# Sheet1.net
KiCad netlist of a schematic drawn in Altium Designer
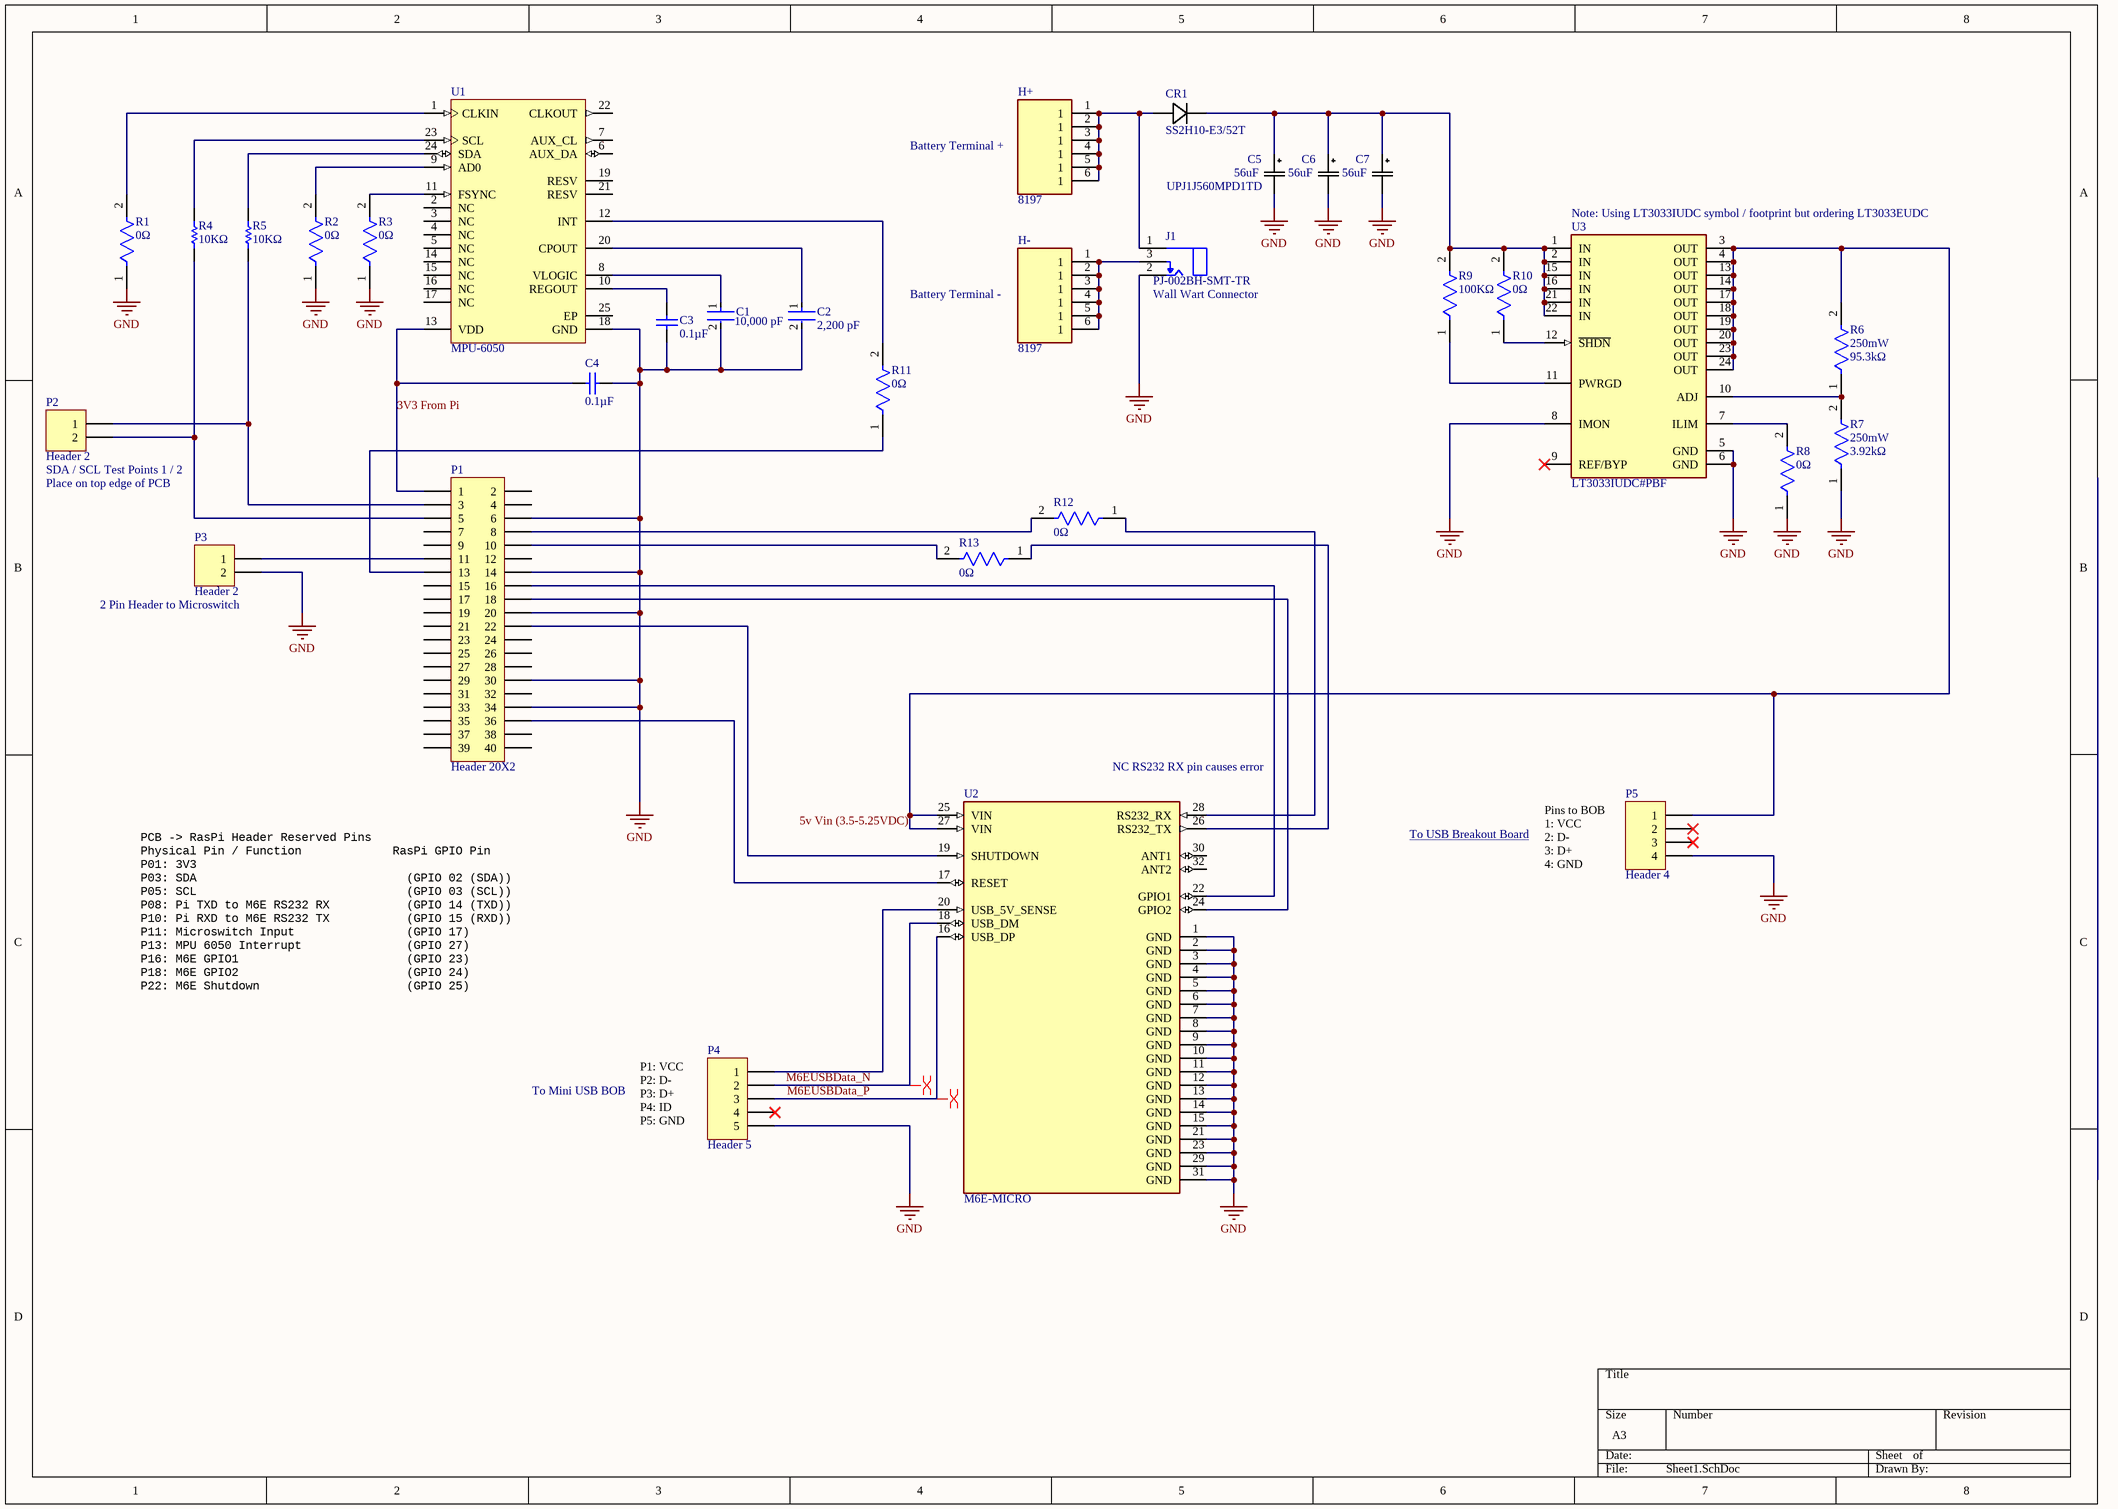
[diagram p0: Sheet1.SchDoc]

(export (version "E")
  (design (tool "Eeschema 10.0.6"))
  (components
    (comp (ref "C1")
      (value "C1206C103K1RACTU")
      (footprint "FP-C1206C-EB-MFG")
      (description "Cap Ceramic 0.01uF 100V X7R 10% SMD 1206 125°C Plastic T/R")
      (fields
        (field (name "MANUFACTURER") "KEMET")
        (field (name "OCTOPART") "https://octopart.com/c1206c103k1ractu-kemet-117927")
        (field (name "CAPACITANCE") "10,000 pF")
      )
      (libsource (lib "Altium Content Vault") (part "b4654b650e69147ec39a6b967a45e02"))
    )
    (comp (ref "C2")
      (value "2,200 pF")
      (footprint "FP-C1206C-EB-MFG")
      (description "CAP CER 2200PF 50V X7R 1206")
      (fields
        (field (name "MANUFACTURER") "KEMET")
        (field (name "MANUFACTURER PART NUMBER") "C1206C222K5RACTU")
      )
      (libsource (lib "Altium Content Vault") (part "b4654b650e69147ec39a6b967a45e02"))
    )
    (comp (ref "C3")
      (value "C1206C104K5RACTU")
      (footprint "KEMT-1206-2_M")
      (description "CAP, Ceramic, 0.1 uF, +/- 10%, 50 V, -55 to 125 degC, 1206 (3216 Metric), RoHS, Tape and Reel")
      (fields (field (name "CAPACITANCE") "0.1µF") (field (name "MANUFACTURER") "Kemet"))
      (libsource (lib "Altium Content Vault") (part "CAP-NP-2"))
    )
    (comp (ref "C4")
      (value "C1206C104K5RACTU")
      (footprint "KEMT-1206-2_M")
      (description "CAP, Ceramic, 0.1 uF, +/- 10%, 50 V, -55 to 125 degC, 1206 (3216 Metric), RoHS, Tape and Reel")
      (fields (field (name "CAPACITANCE") "0.1µF") (field (name "MANUFACTURER") "Kemet"))
      (libsource (lib "Altium Content Vault") (part "CAP-NP-2"))
    )
    (comp (ref "C5")
      (value "UPJ1J560MPD1TD")
      (footprint "CAP_UPJ_8X15_NCH")
      (description "No Description Available")
      (fields
        (field (name "ALTIUM_VALUE") "56uF")
        (field (name "COPYRIGHT") "Copyright (C) 2018 Accelerated Designs. All rights reserved")
      )
      (libsource (lib "56uF_Capacitor") (part "UPJ1J560MPD1TD"))
    )
    (comp (ref "C6")
      (value "56uF")
      (footprint "CAP_UPJ_8X15_NCH")
      (description "No Description Available")
      (fields
        (field (name "MANUFACTURER_PART_NUMBER") "UPJ1J560MPD1TD")
        (field (name "COPYRIGHT") "Copyright (C) 2018 Accelerated Designs. All rights reserved")
      )
      (libsource (lib "56uF_Capacitor") (part "UPJ1J560MPD1TD"))
    )
    (comp (ref "C7")
      (value "56uF")
      (footprint "CAP_UPJ_8X15_NCH")
      (description "No Description Available")
      (fields
        (field (name "MANUFACTURER_PART_NUMBER") "UPJ1J560MPD1TD")
        (field (name "COPYRIGHT") "Copyright (C) 2018 Accelerated Designs. All rights reserved")
      )
      (libsource (lib "56uF_Capacitor") (part "UPJ1J560MPD1TD"))
    )
    (comp (ref "CR1")
      (value "SS2H10-E3/52T")
      (footprint "DIODE_DO214AA")
      (description "No Description Available")
      (fields (field (name "COPYRIGHT") "Copyright (C) 2018 Accelerated Designs. All rights reserved"))
      (libsource (lib "2021-02-16_18-14-03") (part "SS2H10-E3/52T"))
    )
    (comp (ref "H+")
      (value "8197")
      (footprint "KEYSTONE_8197")
      (description "Magnet Neodymium Iron Boron _NdFeB_ 0.500 Dia x 0.750 H _12.7mm x 19.0mm_")
      (fields (field (name "MF") "Radial Magnet"))
      (libsource (lib "8197") (part "8197"))
    )
    (comp (ref "H-")
      (value "8197")
      (footprint "KEYSTONE_8197")
      (description "Magnet Neodymium Iron Boron _NdFeB_ 0.500 Dia x 0.750 H _12.7mm x 19.0mm_")
      (fields (field (name "MF") "Radial Magnet"))
      (libsource (lib "8197") (part "8197"))
    )
    (comp (ref "J1")
      (value "PJ-002BH-SMT-TR")
      (footprint "FP-PJ-002BH-SMT-TR-MFG")
      (description "CONN PWR JACK 2.5X5.5MM SOLDER")
      (fields
        (field (name "MANUFACTURER") "CUI Inc")
        (field (name "OCTOPART") "https://octopart.com/pj-002bh-smt-tr-cui-25947151")
      )
      (libsource (lib "Altium Content Vault") (part "020ff674638626da6de6501228ee46e"))
    )
    (comp (ref "P1")
      (value "Header 20X2")
      (footprint "HDR2X20")
      (description "Header, 20-Pin, Dual row")
      (fields (field (name "PUBLISHER") "Altium Limited"))
      (libsource (lib "Miscellaneous Connectors") (part "Header 20X2"))
    )
    (comp (ref "P2")
      (value "Header 2")
      (footprint "HDR1X2")
      (description "Header, 2-Pin")
      (fields (field (name "PUBLISHER") "Altium Limited"))
      (libsource (lib "Miscellaneous Connectors") (part "Header 2"))
    )
    (comp (ref "P3")
      (value "Header 2")
      (footprint "HDR1X2")
      (description "Header, 2-Pin")
      (fields (field (name "PUBLISHER") "Altium Limited"))
      (libsource (lib "Miscellaneous Connectors") (part "Header 2"))
    )
    (comp (ref "P4")
      (value "Header 5")
      (footprint "HDR1X5")
      (description "Header, 5-Pin")
      (fields (field (name "PUBLISHER") "Altium Limited"))
      (libsource (lib "Miscellaneous Connectors") (part "Header 5"))
    )
    (comp (ref "P5")
      (value "Header 4")
      (footprint "HDR1X4")
      (description "Header, 4-Pin")
      (fields (field (name "PUBLISHER") "Altium Limited"))
      (libsource (lib "Miscellaneous Connectors") (part "Header 4"))
    )
    (comp (ref "R1")
      (value "0Ω")
      (footprint "FP-RC1206-MFG")
      (description "RES SMD 0 OHM JUMPER 1/4W 1206")
      (fields
        (field (name "MANUFACTURER PART NUMBER") "RC1206JR-070RL")
        (field (name "MANUFACTURER") "YAGEO")
      )
      (libsource (lib "Altium Content Vault") (part "1029c3af85768c4190bb7ad29bc67b5"))
    )
    (comp (ref "R2")
      (value "0Ω")
      (footprint "FP-RC1206-MFG")
      (description "RES SMD 0 OHM JUMPER 1/4W 1206")
      (fields
        (field (name "MANUFACTURER PART NUMBER") "RC1206JR-070RL")
        (field (name "MANUFACTURER") "YAGEO")
      )
      (libsource (lib "Altium Content Vault") (part "1029c3af85768c4190bb7ad29bc67b5"))
    )
    (comp (ref "R3")
      (value "0Ω")
      (footprint "FP-RC1206-MFG")
      (description "RES SMD 0 OHM JUMPER 1/4W 1206")
      (fields
        (field (name "MANUFACTURER PART NUMBER") "RC1206JR-070RL")
        (field (name "MANUFACTURER") "YAGEO")
      )
      (libsource (lib "Altium Content Vault") (part "1029c3af85768c4190bb7ad29bc67b5"))
    )
    (comp (ref "R4")
      (value "RC1206FR-0710KL")
      (footprint "RESC3116X65X40ML10T20")
      (description "Chip Resistor, 10 KOhm, +/- 1%, 0.25 W, -55 to 155 degC, 1206 (3216 Metric), RoHS, Tape and Reel")
      (fields
        (field (name "TOLERANCE") "1%")
        (field (name "RESISTANCE") "10KΩ")
        (field (name "MANUFACTURER") "Yageo")
      )
      (libsource (lib "Altium Content Vault") (part "RES-2"))
    )
    (comp (ref "R5")
      (value "RC1206FR-0710KL")
      (footprint "RESC3116X65X40ML10T20")
      (description "Chip Resistor, 10 KOhm, +/- 1%, 0.25 W, -55 to 155 degC, 1206 (3216 Metric), RoHS, Tape and Reel")
      (fields
        (field (name "TOLERANCE") "1%")
        (field (name "RESISTANCE") "10KΩ")
        (field (name "MANUFACTURER") "Yageo")
      )
      (libsource (lib "Altium Content Vault") (part "RES-2"))
    )
    (comp (ref "R6")
      (value "CRCW120695K3FKEA")
      (footprint "FP-CRCW1206-e3-IPC_B")
      (description "RES Thick Film, 95.3kΩ, 1%, 0.25W, 100ppm/°C, 1206")
      (fields
        (field (name "TOLERANCE") "1%")
        (field (name "POWER RATING") "250mW")
        (field (name "RESISTANCE") "95.3kΩ")
      )
      (libsource (lib "Altium Content Vault") (part "1029c3af85768c4190bb7ad29bc67b5"))
    )
    (comp (ref "R7")
      (value "CRCW12063K92FKEA")
      (footprint "FP-CRCW1206-e3-IPC_C")
      (description "RES Thick Film, 3.92kΩ, 1%, 0.25W, 100ppm/°C, 1206")
      (fields
        (field (name "POWER RATING") "250mW")
        (field (name "RESISTANCE") "3.92kΩ")
        (field (name "TOLERANCE") "1%")
      )
      (libsource (lib "Altium Content Vault") (part "1029c3af85768c4190bb7ad29bc67b5"))
    )
    (comp (ref "R8")
      (value "0Ω")
      (footprint "FP-RC1206-MFG")
      (description "RES SMD 0 OHM JUMPER 1/4W 1206")
      (fields
        (field (name "MANUFACTURER PART NUMBER") "RC1206JR-070RL")
        (field (name "MANUFACTURER") "YAGEO")
      )
      (libsource (lib "Altium Content Vault") (part "1029c3af85768c4190bb7ad29bc67b5"))
    )
    (comp (ref "R9")
      (value "100KΩ")
      (footprint "FP-AC1206-MFG")
      (description "RES SMD 100K OHM 1% 1/4W 1206")
      (fields
        (field (name "OCTOPART") "https://octopart.com/ac1206fr-07100kl-yageo-21711116")
        (field (name "MANUFACTURER") "Yageo")
      )
      (libsource (lib "Altium Content Vault") (part "1029c3af85768c4190bb7ad29bc67b5"))
    )
    (comp (ref "R10")
      (value "0Ω")
      (footprint "FP-RC1206-MFG")
      (description "RES SMD 0 OHM JUMPER 1/4W 1206")
      (fields
        (field (name "MANUFACTURER PART NUMBER") "RC1206JR-070RL")
        (field (name "MANUFACTURER") "YAGEO")
      )
      (libsource (lib "Altium Content Vault") (part "1029c3af85768c4190bb7ad29bc67b5"))
    )
    (comp (ref "R11")
      (value "0Ω")
      (footprint "FP-RC1206-MFG")
      (description "RES SMD 0 OHM JUMPER 1/4W 1206")
      (fields
        (field (name "MANUFACTURER PART NUMBER") "RC1206JR-070RL")
        (field (name "MANUFACTURER") "YAGEO")
      )
      (libsource (lib "Altium Content Vault") (part "1029c3af85768c4190bb7ad29bc67b5"))
    )
    (comp (ref "R12")
      (value "0Ω")
      (footprint "FP-RC1206-MFG")
      (description "RES SMD 0 OHM JUMPER 1/4W 1206")
      (fields
        (field (name "MANUFACTURER PART NUMBER") "RC1206JR-070RL")
        (field (name "MANUFACTURER") "YAGEO")
      )
      (libsource (lib "Altium Content Vault") (part "1029c3af85768c4190bb7ad29bc67b5"))
    )
    (comp (ref "R13")
      (value "0Ω")
      (footprint "FP-RC1206-MFG")
      (description "RES SMD 0 OHM JUMPER 1/4W 1206")
      (fields
        (field (name "MANUFACTURER PART NUMBER") "RC1206JR-070RL")
        (field (name "MANUFACTURER") "YAGEO")
      )
      (libsource (lib "Altium Content Vault") (part "1029c3af85768c4190bb7ad29bc67b5"))
    )
    (comp (ref "U1")
      (value "MPU-6050")
      (footprint "IS-QFN-24_V")
      (fields (field (name "MANUFACTURER") "InvenSense"))
      (libsource (lib "Altium Content Vault") (part "IS-MPU-6050-QFN-24"))
    )
    (comp (ref "U2")
      (value "M6E-MICRO")
      (footprint "XCVR_M6E-MICRO")
      (description "KIT DEVELOPMENT M6E MICRO-LTE")
      (fields (field (name "MF") "ThingMagic, a"))
      (libsource (lib "M6E-MICRO") (part "M6E-MICRO"))
    )
    (comp (ref "U3")
      (value "LT3033IUDC#PBF")
      (footprint "FP-UDC-20-05-08-1536-MFG")
      (description "LDO Regulator Pos 0.2V to 9.7V 3A 20-Pin QFN EP Tube")
      (fields (field (name "MANUFACTURER") "Analog Devices"))
      (libsource (lib "Altium Content Vault") (part "32fad297b9cb76d0c6b2a9524b0e8e6"))
    )
  )
  (nets
    (net (code "1") (name "/3V3 From Pi") (class "Default")
      (node (ref "C4") (pin "2") (pinfunction "2_2") (pintype "passive"))
      (node (ref "P1") (pin "1") (pinfunction "1_1") (pintype "passive"))
      (node (ref "U1") (pin "13") (pinfunction "VDD_13") (pintype "power_in"))
    )
    (net (code "2") (name "/5v Vin (3.5-5.25VDC)") (class "Default")
      (node (ref "P5") (pin "1") (pinfunction "1_1") (pintype "passive"))
      (node (ref "R6") (pin "2") (pinfunction "2_2") (pintype "passive"))
      (node (ref "U2") (pin "25") (pinfunction "VIN_25") (pintype "input"))
      (node (ref "U2") (pin "27") (pinfunction "VIN_27") (pintype "input"))
      (node (ref "U3") (pin "13") (pinfunction "OUT_13") (pintype "power_in"))
      (node (ref "U3") (pin "14") (pinfunction "OUT_14") (pintype "power_in"))
      (node (ref "U3") (pin "17") (pinfunction "OUT_17") (pintype "power_in"))
      (node (ref "U3") (pin "18") (pinfunction "OUT_18") (pintype "power_in"))
      (node (ref "U3") (pin "19") (pinfunction "OUT_19") (pintype "power_in"))
      (node (ref "U3") (pin "20") (pinfunction "OUT_20") (pintype "power_in"))
      (node (ref "U3") (pin "23") (pinfunction "OUT_23") (pintype "power_in"))
      (node (ref "U3") (pin "24") (pinfunction "OUT_24") (pintype "power_in"))
      (node (ref "U3") (pin "3") (pinfunction "OUT_3") (pintype "power_in"))
      (node (ref "U3") (pin "4") (pinfunction "OUT_4") (pintype "power_in"))
    )
    (net (code "3") (name "/M6EUSBData_N") (class "Default")
      (node (ref "P4") (pin "2") (pinfunction "2_2") (pintype "passive"))
      (node (ref "U2") (pin "18") (pinfunction "USB_DM_18") (pintype "bidirectional"))
    )
    (net (code "4") (name "/M6EUSBData_P") (class "Default")
      (node (ref "P4") (pin "3") (pinfunction "3_3") (pintype "passive"))
      (node (ref "U2") (pin "16") (pinfunction "USB_DP_16") (pintype "bidirectional"))
    )
    (net (code "5") (name "GND") (class "Default")
      (node (ref "C1") (pin "2") (pinfunction "2_2") (pintype "passive"))
      (node (ref "C2") (pin "2") (pinfunction "2_2") (pintype "passive"))
      (node (ref "C3") (pin "1") (pinfunction "1_1") (pintype "passive"))
      (node (ref "C4") (pin "1") (pinfunction "1_1") (pintype "passive"))
      (node (ref "C5") (pin "2") (pinfunction "2_2") (pintype "passive"))
      (node (ref "C6") (pin "2") (pinfunction "2_2") (pintype "passive"))
      (node (ref "C7") (pin "2") (pinfunction "2_2") (pintype "passive"))
      (node (ref "J1") (pin "2") (pinfunction "2_2") (pintype "passive"))
      (node (ref "P1") (pin "14") (pinfunction "14_14") (pintype "passive"))
      (node (ref "P1") (pin "20") (pinfunction "20_20") (pintype "passive"))
      (node (ref "P1") (pin "30") (pinfunction "30_30") (pintype "passive"))
      (node (ref "P1") (pin "34") (pinfunction "34_34") (pintype "passive"))
      (node (ref "P1") (pin "6") (pinfunction "6_6") (pintype "passive"))
      (node (ref "P3") (pin "2") (pinfunction "2_2") (pintype "passive"))
      (node (ref "P4") (pin "5") (pinfunction "5_5") (pintype "passive"))
      (node (ref "P5") (pin "4") (pinfunction "4_4") (pintype "passive"))
      (node (ref "R1") (pin "1") (pinfunction "1_1") (pintype "passive"))
      (node (ref "R2") (pin "1") (pinfunction "1_1") (pintype "passive"))
      (node (ref "R3") (pin "1") (pinfunction "1_1") (pintype "passive"))
      (node (ref "R7") (pin "1") (pinfunction "1_1") (pintype "passive"))
      (node (ref "R8") (pin "1") (pinfunction "1_1") (pintype "passive"))
      (node (ref "U1") (pin "18") (pinfunction "GND_18") (pintype "power_in"))
      (node (ref "U2") (pin "1") (pinfunction "GND_1") (pintype "power_in"))
      (node (ref "U2") (pin "10") (pinfunction "GND_10") (pintype "power_in"))
      (node (ref "U2") (pin "11") (pinfunction "GND_11") (pintype "power_in"))
      (node (ref "U2") (pin "12") (pinfunction "GND_12") (pintype "power_in"))
      (node (ref "U2") (pin "13") (pinfunction "GND_13") (pintype "power_in"))
      (node (ref "U2") (pin "14") (pinfunction "GND_14") (pintype "power_in"))
      (node (ref "U2") (pin "15") (pinfunction "GND_15") (pintype "power_in"))
      (node (ref "U2") (pin "2") (pinfunction "GND_2") (pintype "power_in"))
      (node (ref "U2") (pin "21") (pinfunction "GND_21") (pintype "power_in"))
      (node (ref "U2") (pin "23") (pinfunction "GND_23") (pintype "power_in"))
      (node (ref "U2") (pin "29") (pinfunction "GND_29") (pintype "power_in"))
      (node (ref "U2") (pin "3") (pinfunction "GND_3") (pintype "power_in"))
      (node (ref "U2") (pin "31") (pinfunction "GND_31") (pintype "power_in"))
      (node (ref "U2") (pin "4") (pinfunction "GND_4") (pintype "power_in"))
      (node (ref "U2") (pin "5") (pinfunction "GND_5") (pintype "power_in"))
      (node (ref "U2") (pin "6") (pinfunction "GND_6") (pintype "power_in"))
      (node (ref "U2") (pin "7") (pinfunction "GND_7") (pintype "power_in"))
      (node (ref "U2") (pin "8") (pinfunction "GND_8") (pintype "power_in"))
      (node (ref "U2") (pin "9") (pinfunction "GND_9") (pintype "power_in"))
      (node (ref "U3") (pin "5") (pinfunction "GND_5") (pintype "power_in"))
      (node (ref "U3") (pin "6") (pinfunction "GND_6") (pintype "power_in"))
      (node (ref "U3") (pin "8") (pinfunction "IMON_8") (pintype "passive"))
    )
    (net (code "6") (name "Net-(C5-Pad1)") (class "Default")
      (node (ref "C5") (pin "1") (pinfunction "1_1") (pintype "passive"))
      (node (ref "C6") (pin "1") (pinfunction "1_1") (pintype "passive"))
      (node (ref "C7") (pin "1") (pinfunction "1_1") (pintype "passive"))
      (node (ref "CR1") (pin "1") (pinfunction "1_1") (pintype "passive"))
      (node (ref "R10") (pin "2") (pinfunction "2_2") (pintype "passive"))
      (node (ref "R9") (pin "2") (pinfunction "2_2") (pintype "passive"))
      (node (ref "U3") (pin "1") (pinfunction "IN_1") (pintype "power_in"))
      (node (ref "U3") (pin "15") (pinfunction "IN_15") (pintype "power_in"))
      (node (ref "U3") (pin "16") (pinfunction "IN_16") (pintype "power_in"))
      (node (ref "U3") (pin "2") (pinfunction "IN_2") (pintype "power_in"))
      (node (ref "U3") (pin "21") (pinfunction "IN_21") (pintype "power_in"))
      (node (ref "U3") (pin "22") (pinfunction "IN_22") (pintype "power_in"))
    )
    (net (code "7") (name "Net-(CR1-Pad2)") (class "Default")
      (node (ref "CR1") (pin "2") (pinfunction "2_2") (pintype "passive"))
      (node (ref "H+") (pin "1") (pinfunction "1_1") (pintype "passive"))
      (node (ref "H+") (pin "2") (pinfunction "1_2") (pintype "passive"))
      (node (ref "H+") (pin "3") (pinfunction "1_3") (pintype "passive"))
      (node (ref "H+") (pin "4") (pinfunction "1_4") (pintype "passive"))
      (node (ref "H+") (pin "5") (pinfunction "1_5") (pintype "passive"))
      (node (ref "H+") (pin "6") (pinfunction "1_6") (pintype "passive"))
      (node (ref "J1") (pin "1") (pinfunction "1_1") (pintype "passive"))
    )
    (net (code "8") (name "Net-(H--1-Pad2)") (class "Default")
      (node (ref "H-") (pin "1") (pinfunction "1_1") (pintype "passive"))
      (node (ref "H-") (pin "2") (pinfunction "1_2") (pintype "passive"))
      (node (ref "H-") (pin "3") (pinfunction "1_3") (pintype "passive"))
      (node (ref "H-") (pin "4") (pinfunction "1_4") (pintype "passive"))
      (node (ref "H-") (pin "5") (pinfunction "1_5") (pintype "passive"))
      (node (ref "H-") (pin "6") (pinfunction "1_6") (pintype "passive"))
      (node (ref "J1") (pin "3") (pinfunction "3_3") (pintype "passive"))
    )
    (net (code "9") (name "Net-(P1-Pad3)") (class "Default")
      (node (ref "P1") (pin "3") (pinfunction "3_3") (pintype "passive"))
      (node (ref "P2") (pin "1") (pinfunction "1_1") (pintype "passive"))
      (node (ref "R5") (pin "1") (pinfunction "1_1") (pintype "passive"))
    )
    (net (code "10") (name "Net-(P1-Pad5)") (class "Default")
      (node (ref "P1") (pin "5") (pinfunction "5_5") (pintype "passive"))
      (node (ref "P2") (pin "2") (pinfunction "2_2") (pintype "passive"))
      (node (ref "R4") (pin "1") (pinfunction "1_1") (pintype "passive"))
    )
    (net (code "11") (name "Net-(P1-Pad8)") (class "Default")
      (node (ref "P1") (pin "8") (pinfunction "8_8") (pintype "passive"))
      (node (ref "R12") (pin "2") (pinfunction "2_2") (pintype "passive"))
    )
    (net (code "12") (name "Net-(P1-Pad10)") (class "Default")
      (node (ref "P1") (pin "10") (pinfunction "10_10") (pintype "passive"))
      (node (ref "R13") (pin "2") (pinfunction "2_2") (pintype "passive"))
    )
    (net (code "13") (name "Net-(P1-Pad11)") (class "Default")
      (node (ref "P1") (pin "11") (pinfunction "11_11") (pintype "passive"))
      (node (ref "P3") (pin "1") (pinfunction "1_1") (pintype "passive"))
    )
    (net (code "14") (name "Net-(P1-Pad13)") (class "Default")
      (node (ref "P1") (pin "13") (pinfunction "13_13") (pintype "passive"))
      (node (ref "R11") (pin "1") (pinfunction "1_1") (pintype "passive"))
    )
    (net (code "15") (name "Net-(U1-AD0)") (class "Default")
      (node (ref "R2") (pin "2") (pinfunction "2_2") (pintype "passive"))
      (node (ref "U1") (pin "9") (pinfunction "AD0_9") (pintype "input"))
    )
    (net (code "16") (name "Net-(U1-CLKIN)") (class "Default")
      (node (ref "R1") (pin "2") (pinfunction "2_2") (pintype "passive"))
      (node (ref "U1") (pin "1") (pinfunction "CLKIN_1") (pintype "input"))
    )
    (net (code "17") (name "Net-(U1-CPOUT)") (class "Default")
      (node (ref "C2") (pin "1") (pinfunction "1_1") (pintype "passive"))
      (node (ref "U1") (pin "20") (pinfunction "CPOUT_20") (pintype "passive"))
    )
    (net (code "18") (name "Net-(U1-FSYNC)") (class "Default")
      (node (ref "R3") (pin "2") (pinfunction "2_2") (pintype "passive"))
      (node (ref "U1") (pin "11") (pinfunction "FSYNC_11") (pintype "input"))
    )
    (net (code "19") (name "Net-(U1-INT)") (class "Default")
      (node (ref "R11") (pin "2") (pinfunction "2_2") (pintype "passive"))
      (node (ref "U1") (pin "12") (pinfunction "INT_12") (pintype "open_collector"))
    )
    (net (code "20") (name "Net-(U1-REGOUT)") (class "Default")
      (node (ref "C3") (pin "2") (pinfunction "2_2") (pintype "passive"))
      (node (ref "U1") (pin "10") (pinfunction "REGOUT_10") (pintype "passive"))
    )
    (net (code "21") (name "Net-(U1-SCL)") (class "Default")
      (node (ref "R4") (pin "2") (pinfunction "2_2") (pintype "passive"))
      (node (ref "U1") (pin "23") (pinfunction "SCL_23") (pintype "input"))
    )
    (net (code "22") (name "Net-(U1-SDA)") (class "Default")
      (node (ref "R5") (pin "2") (pinfunction "2_2") (pintype "passive"))
      (node (ref "U1") (pin "24") (pinfunction "SDA_24") (pintype "bidirectional"))
    )
    (net (code "23") (name "Net-(U1-VLOGIC)") (class "Default")
      (node (ref "C1") (pin "1") (pinfunction "1_1") (pintype "passive"))
      (node (ref "U1") (pin "8") (pinfunction "VLOGIC_8") (pintype "power_in"))
    )
    (net (code "24") (name "Net-(U2-GPIO1)") (class "Default")
      (node (ref "P1") (pin "16") (pinfunction "16_16") (pintype "passive"))
      (node (ref "U2") (pin "22") (pinfunction "GPIO1_22") (pintype "bidirectional"))
    )
    (net (code "25") (name "Net-(U2-GPIO2)") (class "Default")
      (node (ref "P1") (pin "18") (pinfunction "18_18") (pintype "passive"))
      (node (ref "U2") (pin "24") (pinfunction "GPIO2_24") (pintype "bidirectional"))
    )
    (net (code "26") (name "Net-(U2-RESET)") (class "Default")
      (node (ref "P1") (pin "36") (pinfunction "36_36") (pintype "passive"))
      (node (ref "U2") (pin "17") (pinfunction "RESET_17") (pintype "bidirectional"))
    )
    (net (code "27") (name "Net-(U2-RS232_RX)") (class "Default")
      (node (ref "R12") (pin "1") (pinfunction "1_1") (pintype "passive"))
      (node (ref "U2") (pin "28") (pinfunction "RS232_RX_28") (pintype "input"))
    )
    (net (code "28") (name "Net-(U2-RS232_TX)") (class "Default")
      (node (ref "R13") (pin "1") (pinfunction "1_1") (pintype "passive"))
      (node (ref "U2") (pin "26") (pinfunction "RS232_TX_26") (pintype "output"))
    )
    (net (code "29") (name "Net-(U2-SHUTDOWN)") (class "Default")
      (node (ref "P1") (pin "22") (pinfunction "22_22") (pintype "passive"))
      (node (ref "U2") (pin "19") (pinfunction "SHUTDOWN_19") (pintype "input"))
    )
    (net (code "30") (name "Net-(U2-USB_5V_SENSE)") (class "Default")
      (node (ref "P4") (pin "1") (pinfunction "1_1") (pintype "passive"))
      (node (ref "U2") (pin "20") (pinfunction "USB_5V_SENSE_20") (pintype "input"))
    )
    (net (code "31") (name "Net-(U3-ADJ)") (class "Default")
      (node (ref "R6") (pin "1") (pinfunction "1_1") (pintype "passive"))
      (node (ref "R7") (pin "2") (pinfunction "2_2") (pintype "passive"))
      (node (ref "U3") (pin "10") (pinfunction "ADJ_10") (pintype "passive"))
    )
    (net (code "32") (name "Net-(U3-ILIM)") (class "Default")
      (node (ref "R8") (pin "2") (pinfunction "2_2") (pintype "passive"))
      (node (ref "U3") (pin "7") (pinfunction "ILIM_7") (pintype "passive"))
    )
    (net (code "33") (name "Net-(U3-PWRGD)") (class "Default")
      (node (ref "R9") (pin "1") (pinfunction "1_1") (pintype "passive"))
      (node (ref "U3") (pin "11") (pinfunction "PWRGD_11") (pintype "open_collector"))
    )
    (net (code "34") (name "Net-(U3-~{SHDN})") (class "Default")
      (node (ref "R10") (pin "1") (pinfunction "1_1") (pintype "passive"))
      (node (ref "U3") (pin "12") (pinfunction "~{SHDN}_12") (pintype "input"))
    )
    (net (code "35") (name "unconnected-(P1-Pad2)") (class "Default")
      (node (ref "P1") (pin "2") (pinfunction "2_2") (pintype "passive"))
    )
    (net (code "36") (name "unconnected-(P1-Pad4)") (class "Default")
      (node (ref "P1") (pin "4") (pinfunction "4_4") (pintype "passive"))
    )
    (net (code "37") (name "unconnected-(P1-Pad7)") (class "Default")
      (node (ref "P1") (pin "7") (pinfunction "7_7") (pintype "passive"))
    )
    (net (code "38") (name "unconnected-(P1-Pad9)") (class "Default")
      (node (ref "P1") (pin "9") (pinfunction "9_9") (pintype "passive"))
    )
    (net (code "39") (name "unconnected-(P1-Pad12)") (class "Default")
      (node (ref "P1") (pin "12") (pinfunction "12_12") (pintype "passive"))
    )
    (net (code "40") (name "unconnected-(P1-Pad15)") (class "Default")
      (node (ref "P1") (pin "15") (pinfunction "15_15") (pintype "passive"))
    )
    (net (code "41") (name "unconnected-(P1-Pad17)") (class "Default")
      (node (ref "P1") (pin "17") (pinfunction "17_17") (pintype "passive"))
    )
    (net (code "42") (name "unconnected-(P1-Pad19)") (class "Default")
      (node (ref "P1") (pin "19") (pinfunction "19_19") (pintype "passive"))
    )
    (net (code "43") (name "unconnected-(P1-Pad21)") (class "Default")
      (node (ref "P1") (pin "21") (pinfunction "21_21") (pintype "passive"))
    )
    (net (code "44") (name "unconnected-(P1-Pad23)") (class "Default")
      (node (ref "P1") (pin "23") (pinfunction "23_23") (pintype "passive"))
    )
    (net (code "45") (name "unconnected-(P1-Pad24)") (class "Default")
      (node (ref "P1") (pin "24") (pinfunction "24_24") (pintype "passive"))
    )
    (net (code "46") (name "unconnected-(P1-Pad25)") (class "Default")
      (node (ref "P1") (pin "25") (pinfunction "25_25") (pintype "passive"))
    )
    (net (code "47") (name "unconnected-(P1-Pad26)") (class "Default")
      (node (ref "P1") (pin "26") (pinfunction "26_26") (pintype "passive"))
    )
    (net (code "48") (name "unconnected-(P1-Pad27)") (class "Default")
      (node (ref "P1") (pin "27") (pinfunction "27_27") (pintype "passive"))
    )
    (net (code "49") (name "unconnected-(P1-Pad28)") (class "Default")
      (node (ref "P1") (pin "28") (pinfunction "28_28") (pintype "passive"))
    )
    (net (code "50") (name "unconnected-(P1-Pad29)") (class "Default")
      (node (ref "P1") (pin "29") (pinfunction "29_29") (pintype "passive"))
    )
    (net (code "51") (name "unconnected-(P1-Pad31)") (class "Default")
      (node (ref "P1") (pin "31") (pinfunction "31_31") (pintype "passive"))
    )
    (net (code "52") (name "unconnected-(P1-Pad32)") (class "Default")
      (node (ref "P1") (pin "32") (pinfunction "32_32") (pintype "passive"))
    )
    (net (code "53") (name "unconnected-(P1-Pad33)") (class "Default")
      (node (ref "P1") (pin "33") (pinfunction "33_33") (pintype "passive"))
    )
    (net (code "54") (name "unconnected-(P1-Pad35)") (class "Default")
      (node (ref "P1") (pin "35") (pinfunction "35_35") (pintype "passive"))
    )
    (net (code "55") (name "unconnected-(P1-Pad37)") (class "Default")
      (node (ref "P1") (pin "37") (pinfunction "37_37") (pintype "passive"))
    )
    (net (code "56") (name "unconnected-(P1-Pad38)") (class "Default")
      (node (ref "P1") (pin "38") (pinfunction "38_38") (pintype "passive"))
    )
    (net (code "57") (name "unconnected-(P1-Pad39)") (class "Default")
      (node (ref "P1") (pin "39") (pinfunction "39_39") (pintype "passive"))
    )
    (net (code "58") (name "unconnected-(P1-Pad40)") (class "Default")
      (node (ref "P1") (pin "40") (pinfunction "40_40") (pintype "passive"))
    )
    (net (code "59") (name "unconnected-(P4-Pad4)") (class "Default")
      (node (ref "P4") (pin "4") (pinfunction "4_4") (pintype "passive+no_connect"))
    )
    (net (code "60") (name "unconnected-(P5-Pad2)") (class "Default")
      (node (ref "P5") (pin "2") (pinfunction "2_2") (pintype "passive+no_connect"))
    )
    (net (code "61") (name "unconnected-(P5-Pad3)") (class "Default")
      (node (ref "P5") (pin "3") (pinfunction "3_3") (pintype "passive+no_connect"))
    )
    (net (code "62") (name "unconnected-(U1-AUX_CL-Pad7)") (class "Default")
      (node (ref "U1") (pin "7") (pinfunction "AUX_CL_7") (pintype "output"))
    )
    (net (code "63") (name "unconnected-(U1-AUX_DA-Pad6)") (class "Default")
      (node (ref "U1") (pin "6") (pinfunction "AUX_DA_6") (pintype "bidirectional"))
    )
    (net (code "64") (name "unconnected-(U1-CLKOUT-Pad22)") (class "Default")
      (node (ref "U1") (pin "22") (pinfunction "CLKOUT_22") (pintype "output"))
    )
    (net (code "65") (name "unconnected-(U1-EP-Pad25)") (class "Default")
      (node (ref "U1") (pin "25") (pinfunction "EP_25") (pintype "power_in"))
    )
    (net (code "66") (name "unconnected-(U1-NC-Pad2)") (class "Default")
      (node (ref "U1") (pin "2") (pinfunction "NC_2") (pintype "passive"))
    )
    (net (code "67") (name "unconnected-(U1-NC-Pad3)") (class "Default")
      (node (ref "U1") (pin "3") (pinfunction "NC_3") (pintype "passive"))
    )
    (net (code "68") (name "unconnected-(U1-NC-Pad4)") (class "Default")
      (node (ref "U1") (pin "4") (pinfunction "NC_4") (pintype "passive"))
    )
    (net (code "69") (name "unconnected-(U1-NC-Pad5)") (class "Default")
      (node (ref "U1") (pin "5") (pinfunction "NC_5") (pintype "passive"))
    )
    (net (code "70") (name "unconnected-(U1-NC-Pad14)") (class "Default")
      (node (ref "U1") (pin "14") (pinfunction "NC_14") (pintype "passive"))
    )
    (net (code "71") (name "unconnected-(U1-NC-Pad15)") (class "Default")
      (node (ref "U1") (pin "15") (pinfunction "NC_15") (pintype "passive"))
    )
    (net (code "72") (name "unconnected-(U1-NC-Pad16)") (class "Default")
      (node (ref "U1") (pin "16") (pinfunction "NC_16") (pintype "passive"))
    )
    (net (code "73") (name "unconnected-(U1-NC-Pad17)") (class "Default")
      (node (ref "U1") (pin "17") (pinfunction "NC_17") (pintype "passive"))
    )
    (net (code "74") (name "unconnected-(U1-RESV-Pad19)") (class "Default")
      (node (ref "U1") (pin "19") (pinfunction "RESV_19") (pintype "passive"))
    )
    (net (code "75") (name "unconnected-(U1-RESV-Pad21)") (class "Default")
      (node (ref "U1") (pin "21") (pinfunction "RESV_21") (pintype "passive"))
    )
    (net (code "76") (name "unconnected-(U2-ANT1-Pad30)") (class "Default")
      (node (ref "U2") (pin "30") (pinfunction "ANT1_30") (pintype "bidirectional"))
    )
    (net (code "77") (name "unconnected-(U2-ANT2-Pad32)") (class "Default")
      (node (ref "U2") (pin "32") (pinfunction "ANT2_32") (pintype "bidirectional"))
    )
    (net (code "78") (name "unconnected-(U3-REF{slash}BYP-Pad9)") (class "Default")
      (node (ref "U3") (pin "9") (pinfunction "REF/BYP_9") (pintype "passive+no_connect"))
    )
  )
)
